# interface.net
KiCad netlist of a schematic drawn in Altium Designer
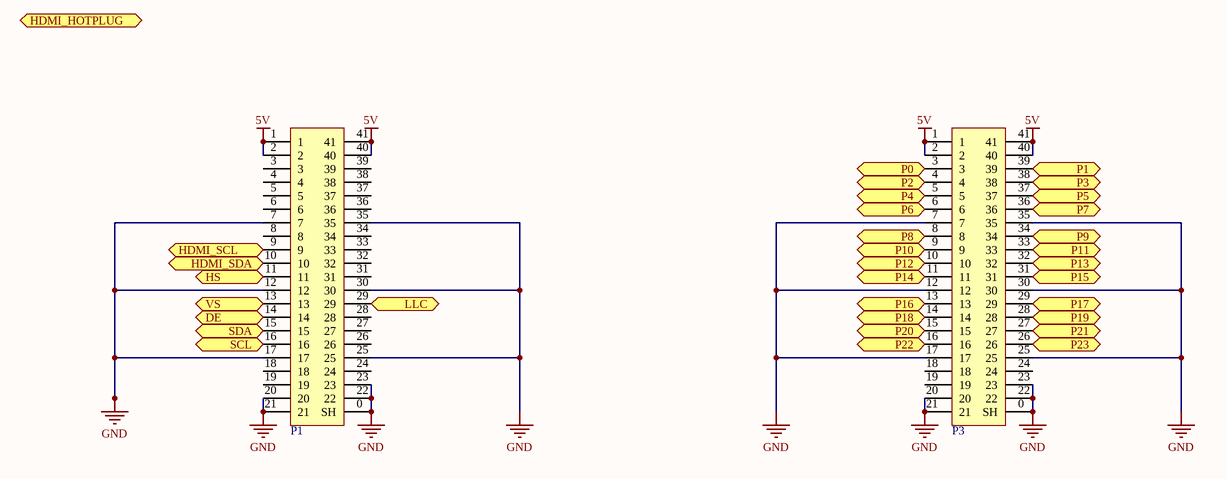
[diagram p0: interface.SchDoc]

(export (version "E")
  (design (tool "Eeschema 10.0.6"))
  (components
    (comp (ref "P1") (value "DF9-41S") (footprint "DF9-41S") (libsource (lib "cyusb3014") (part "DF9-41S")))
    (comp (ref "P3") (value "DF9-41S") (footprint "DF9-41S") (libsource (lib "cyusb3014") (part "DF9-41S")))
  )
  (nets
    (net (code "1") (name "/DE") (class "Default")
      (node (ref "P1") (pin "14") (pinfunction "14_14") (pintype "passive"))
    )
    (net (code "3") (name "/HDMI_SCL") (class "Default")
      (node (ref "P1") (pin "9") (pinfunction "9_9") (pintype "passive"))
    )
    (net (code "4") (name "/HDMI_SDA") (class "Default")
      (node (ref "P1") (pin "10") (pinfunction "10_10") (pintype "passive"))
    )
    (net (code "5") (name "/HS") (class "Default")
      (node (ref "P1") (pin "11") (pinfunction "11_11") (pintype "passive"))
    )
    (net (code "6") (name "/LLC") (class "Default")
      (node (ref "P1") (pin "29") (pinfunction "29_29") (pintype "passive"))
    )
    (net (code "7") (name "/P0") (class "Default")
      (node (ref "P3") (pin "3") (pinfunction "3_3") (pintype "passive"))
    )
    (net (code "8") (name "/P1") (class "Default")
      (node (ref "P3") (pin "39") (pinfunction "39_39") (pintype "passive"))
    )
    (net (code "9") (name "/P2") (class "Default")
      (node (ref "P3") (pin "4") (pinfunction "4_4") (pintype "passive"))
    )
    (net (code "10") (name "/P3") (class "Default")
      (node (ref "P3") (pin "38") (pinfunction "38_38") (pintype "passive"))
    )
    (net (code "11") (name "/P4") (class "Default")
      (node (ref "P3") (pin "5") (pinfunction "5_5") (pintype "passive"))
    )
    (net (code "12") (name "/P5") (class "Default")
      (node (ref "P3") (pin "37") (pinfunction "37_37") (pintype "passive"))
    )
    (net (code "13") (name "/P6") (class "Default")
      (node (ref "P3") (pin "6") (pinfunction "6_6") (pintype "passive"))
    )
    (net (code "14") (name "/P7") (class "Default")
      (node (ref "P3") (pin "36") (pinfunction "36_36") (pintype "passive"))
    )
    (net (code "15") (name "/P8") (class "Default")
      (node (ref "P3") (pin "8") (pinfunction "8_8") (pintype "passive"))
    )
    (net (code "16") (name "/P9") (class "Default")
      (node (ref "P3") (pin "34") (pinfunction "34_34") (pintype "passive"))
    )
    (net (code "17") (name "/P10") (class "Default")
      (node (ref "P3") (pin "9") (pinfunction "9_9") (pintype "passive"))
    )
    (net (code "18") (name "/P11") (class "Default")
      (node (ref "P3") (pin "33") (pinfunction "33_33") (pintype "passive"))
    )
    (net (code "19") (name "/P12") (class "Default")
      (node (ref "P3") (pin "10") (pinfunction "10_10") (pintype "passive"))
    )
    (net (code "20") (name "/P13") (class "Default")
      (node (ref "P3") (pin "32") (pinfunction "32_32") (pintype "passive"))
    )
    (net (code "21") (name "/P14") (class "Default")
      (node (ref "P3") (pin "11") (pinfunction "11_11") (pintype "passive"))
    )
    (net (code "22") (name "/P15") (class "Default")
      (node (ref "P3") (pin "31") (pinfunction "31_31") (pintype "passive"))
    )
    (net (code "23") (name "/P16") (class "Default")
      (node (ref "P3") (pin "13") (pinfunction "13_13") (pintype "passive"))
    )
    (net (code "24") (name "/P17") (class "Default")
      (node (ref "P3") (pin "29") (pinfunction "29_29") (pintype "passive"))
    )
    (net (code "25") (name "/P18") (class "Default")
      (node (ref "P3") (pin "14") (pinfunction "14_14") (pintype "passive"))
    )
    (net (code "26") (name "/P19") (class "Default")
      (node (ref "P3") (pin "28") (pinfunction "28_28") (pintype "passive"))
    )
    (net (code "27") (name "/P20") (class "Default")
      (node (ref "P3") (pin "15") (pinfunction "15_15") (pintype "passive"))
    )
    (net (code "28") (name "/P21") (class "Default")
      (node (ref "P3") (pin "27") (pinfunction "27_27") (pintype "passive"))
    )
    (net (code "29") (name "/P22") (class "Default")
      (node (ref "P3") (pin "16") (pinfunction "16_16") (pintype "passive"))
    )
    (net (code "30") (name "/P23") (class "Default")
      (node (ref "P3") (pin "26") (pinfunction "26_26") (pintype "passive"))
    )
    (net (code "31") (name "/SCL") (class "Default")
      (node (ref "P1") (pin "16") (pinfunction "16_16") (pintype "passive"))
    )
    (net (code "32") (name "/SDA") (class "Default")
      (node (ref "P1") (pin "15") (pinfunction "15_15") (pintype "passive"))
    )
    (net (code "33") (name "/VS") (class "Default")
      (node (ref "P1") (pin "13") (pinfunction "13_13") (pintype "passive"))
    )
    (net (code "34") (name "5V") (class "Default")
      (node (ref "P1") (pin "1") (pinfunction "1_1") (pintype "passive"))
      (node (ref "P1") (pin "2") (pinfunction "2_2") (pintype "passive"))
      (node (ref "P1") (pin "40") (pinfunction "40_40") (pintype "passive"))
      (node (ref "P1") (pin "41") (pinfunction "41_41") (pintype "passive"))
      (node (ref "P3") (pin "1") (pinfunction "1_1") (pintype "passive"))
      (node (ref "P3") (pin "2") (pinfunction "2_2") (pintype "passive"))
      (node (ref "P3") (pin "40") (pinfunction "40_40") (pintype "passive"))
      (node (ref "P3") (pin "41") (pinfunction "41_41") (pintype "passive"))
    )
    (net (code "35") (name "GND") (class "Default")
      (node (ref "P1") (pin "0") (pinfunction "SH_0") (pintype "passive"))
      (node (ref "P1") (pin "12") (pinfunction "12_12") (pintype "passive"))
      (node (ref "P1") (pin "17") (pinfunction "17_17") (pintype "passive"))
      (node (ref "P1") (pin "20") (pinfunction "20_20") (pintype "passive"))
      (node (ref "P1") (pin "21") (pinfunction "21_21") (pintype "passive"))
      (node (ref "P1") (pin "22") (pinfunction "22_22") (pintype "passive"))
      (node (ref "P1") (pin "23") (pinfunction "23_23") (pintype "passive"))
      (node (ref "P1") (pin "25") (pinfunction "25_25") (pintype "passive"))
      (node (ref "P1") (pin "30") (pinfunction "30_30") (pintype "passive"))
      (node (ref "P1") (pin "35") (pinfunction "35_35") (pintype "passive"))
      (node (ref "P1") (pin "7") (pinfunction "7_7") (pintype "passive"))
      (node (ref "P3") (pin "0") (pinfunction "SH_0") (pintype "passive"))
      (node (ref "P3") (pin "12") (pinfunction "12_12") (pintype "passive"))
      (node (ref "P3") (pin "17") (pinfunction "17_17") (pintype "passive"))
      (node (ref "P3") (pin "20") (pinfunction "20_20") (pintype "passive"))
      (node (ref "P3") (pin "21") (pinfunction "21_21") (pintype "passive"))
      (node (ref "P3") (pin "22") (pinfunction "22_22") (pintype "passive"))
      (node (ref "P3") (pin "23") (pinfunction "23_23") (pintype "passive"))
      (node (ref "P3") (pin "25") (pinfunction "25_25") (pintype "passive"))
      (node (ref "P3") (pin "30") (pinfunction "30_30") (pintype "passive"))
      (node (ref "P3") (pin "35") (pinfunction "35_35") (pintype "passive"))
      (node (ref "P3") (pin "7") (pinfunction "7_7") (pintype "passive"))
    )
    (net (code "36") (name "unconnected-(P1-Pad3)") (class "Default")
      (node (ref "P1") (pin "3") (pinfunction "3_3") (pintype "passive"))
    )
    (net (code "37") (name "unconnected-(P1-Pad4)") (class "Default")
      (node (ref "P1") (pin "4") (pinfunction "4_4") (pintype "passive"))
    )
    (net (code "38") (name "unconnected-(P1-Pad5)") (class "Default")
      (node (ref "P1") (pin "5") (pinfunction "5_5") (pintype "passive"))
    )
    (net (code "39") (name "unconnected-(P1-Pad6)") (class "Default")
      (node (ref "P1") (pin "6") (pinfunction "6_6") (pintype "passive"))
    )
    (net (code "40") (name "unconnected-(P1-Pad8)") (class "Default")
      (node (ref "P1") (pin "8") (pinfunction "8_8") (pintype "passive"))
    )
    (net (code "41") (name "unconnected-(P1-Pad18)") (class "Default")
      (node (ref "P1") (pin "18") (pinfunction "18_18") (pintype "passive"))
    )
    (net (code "42") (name "unconnected-(P1-Pad19)") (class "Default")
      (node (ref "P1") (pin "19") (pinfunction "19_19") (pintype "passive"))
    )
    (net (code "43") (name "unconnected-(P1-Pad24)") (class "Default")
      (node (ref "P1") (pin "24") (pinfunction "24_24") (pintype "passive"))
    )
    (net (code "44") (name "unconnected-(P1-Pad26)") (class "Default")
      (node (ref "P1") (pin "26") (pinfunction "26_26") (pintype "passive"))
    )
    (net (code "45") (name "unconnected-(P1-Pad27)") (class "Default")
      (node (ref "P1") (pin "27") (pinfunction "27_27") (pintype "passive"))
    )
    (net (code "46") (name "unconnected-(P1-Pad28)") (class "Default")
      (node (ref "P1") (pin "28") (pinfunction "28_28") (pintype "passive"))
    )
    (net (code "47") (name "unconnected-(P1-Pad31)") (class "Default")
      (node (ref "P1") (pin "31") (pinfunction "31_31") (pintype "passive"))
    )
    (net (code "48") (name "unconnected-(P1-Pad32)") (class "Default")
      (node (ref "P1") (pin "32") (pinfunction "32_32") (pintype "passive"))
    )
    (net (code "49") (name "unconnected-(P1-Pad33)") (class "Default")
      (node (ref "P1") (pin "33") (pinfunction "33_33") (pintype "passive"))
    )
    (net (code "50") (name "unconnected-(P1-Pad34)") (class "Default")
      (node (ref "P1") (pin "34") (pinfunction "34_34") (pintype "passive"))
    )
    (net (code "51") (name "unconnected-(P1-Pad36)") (class "Default")
      (node (ref "P1") (pin "36") (pinfunction "36_36") (pintype "passive"))
    )
    (net (code "52") (name "unconnected-(P1-Pad37)") (class "Default")
      (node (ref "P1") (pin "37") (pinfunction "37_37") (pintype "passive"))
    )
    (net (code "53") (name "unconnected-(P1-Pad38)") (class "Default")
      (node (ref "P1") (pin "38") (pinfunction "38_38") (pintype "passive"))
    )
    (net (code "54") (name "unconnected-(P1-Pad39)") (class "Default")
      (node (ref "P1") (pin "39") (pinfunction "39_39") (pintype "passive"))
    )
    (net (code "55") (name "unconnected-(P3-Pad18)") (class "Default")
      (node (ref "P3") (pin "18") (pinfunction "18_18") (pintype "passive"))
    )
    (net (code "56") (name "unconnected-(P3-Pad19)") (class "Default")
      (node (ref "P3") (pin "19") (pinfunction "19_19") (pintype "passive"))
    )
    (net (code "57") (name "unconnected-(P3-Pad24)") (class "Default")
      (node (ref "P3") (pin "24") (pinfunction "24_24") (pintype "passive"))
    )
  )
)
